# thermokoppel.net
KiCad netlist of a schematic drawn in Altium Designer
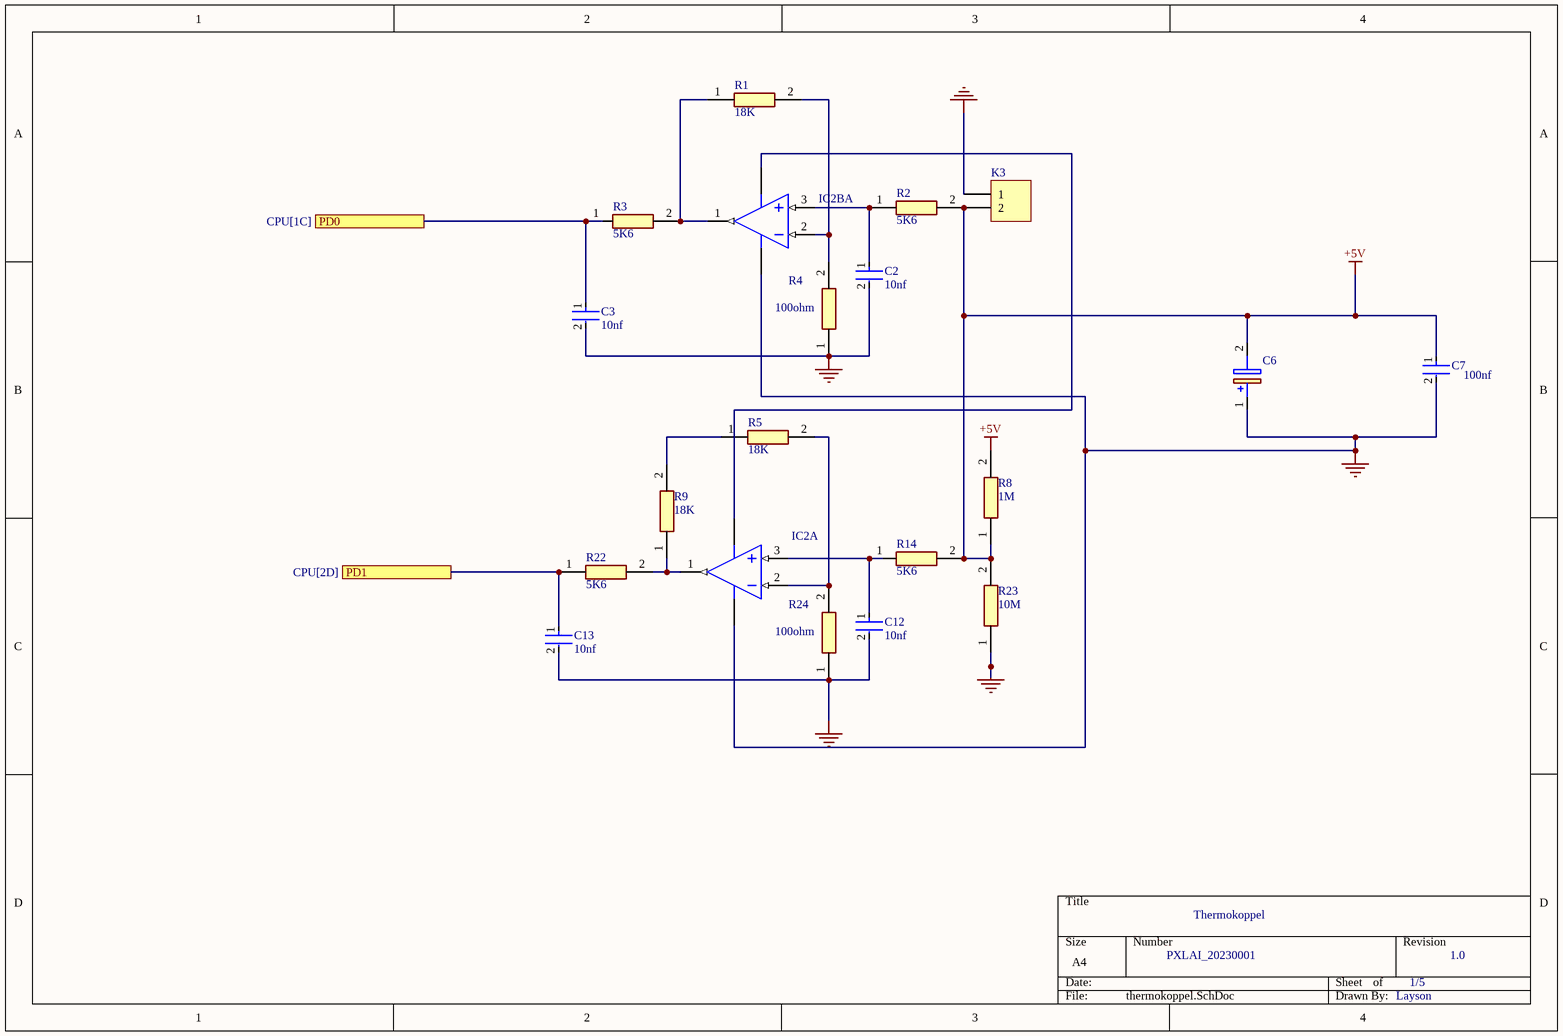
[diagram p0: thermokoppel.SchDoc]

(export (version "E")
  (design (tool "Eeschema 10.0.6"))
  (components
    (comp (ref "C2")
      (value "10nf")
      (footprint "FP-RDE0M1-MFG")
      (description "Ceramic Capacitor 10nF ±10% 50V X7R Radial")
      (fields (field (name "TOLERANCE") "10%"))
      (libsource (lib "Altium Content Vault") (part "b4654b650e69147ec39a6b967a45e02"))
    )
    (comp (ref "C3")
      (value "10nf")
      (footprint "FP-RDE0M1-MFG")
      (description "Ceramic Capacitor 10nF ±10% 50V X7R Radial")
      (fields (field (name "TOLERANCE") "10%"))
      (libsource (lib "Altium Content Vault") (part "b4654b650e69147ec39a6b967a45e02"))
    )
    (comp (ref "C6")
      (value "MCGPR50V106M5X11")
      (footprint "SamacSys:CAPPRD200W52D525H1200")
      (description "Capacitor Polarised")
      (libsource (lib "*") (part "MCGPR50V106M5X11"))
    )
    (comp (ref "C7")
      (value "100nf")
      (footprint "FP-C0402-BB-MFG")
      (description "CAP CER 0.1UF 10V X5R 0402")
      (fields (field (name "MANUFACTURER") "Kemet") (field (name "TOLERANCE") "0.1"))
      (libsource (lib "Altium Content Vault") (part "b4654b650e69147ec39a6b967a45e02"))
    )
    (comp (ref "C12")
      (value "10nf")
      (footprint "FP-RDE0M1-MFG")
      (description "Ceramic Capacitor 10nF ±10% 50V X7R Radial")
      (fields (field (name "TOLERANCE") "10%"))
      (libsource (lib "Altium Content Vault") (part "b4654b650e69147ec39a6b967a45e02"))
    )
    (comp (ref "C13")
      (value "10nf")
      (footprint "FP-RDE0M1-MFG")
      (description "Ceramic Capacitor 10nF ±10% 50V X7R Radial")
      (fields (field (name "TOLERANCE") "10%"))
      (libsource (lib "Altium Content Vault") (part "b4654b650e69147ec39a6b967a45e02"))
    )
    (comp (ref "IC2")
      (value "IC2A")
      (footprint "SOIC-SN8_M")
      (description "None")
      (libsource (lib "Altium Content Vault") (part "AMP-OPA-MCP6002-IL8"))
    )
    (comp (ref "IC2B")
      (value "MCP6002-E/MS")
      (footprint "MSOP-MS8_M")
      (description "None")
      (libsource (lib "") (part "AMP-OPA-MCP6002-IL8_1"))
    )
    (comp (ref "K3")
      (value "Header 2")
      (footprint "HDR1X2")
      (description "Header, 2-Pin")
      (fields (field (name "PUBLISHER") "Altium Limited"))
      (libsource (lib "Miscellaneous Connectors") (part "Header 2"))
    )
    (comp (ref "R1")
      (value "18K")
      (footprint "SamacSys:RESC2012X65N")
      (description "Resistor\r\nCPF0805B18KE")
      (fields
        (field (name "MANUFACTURER_PART_NUMBER") "CPF0805B18KE")
        (field (name "MOUSER PART NUMBER") "279-CPF0805B18KE")
      )
      (libsource (lib "*") (part "CPF0805B18KE"))
    )
    (comp (ref "R2")
      (value "5K6")
      (footprint "SamacSys:RESC2012X65N")
      (description "Resistor\r\nCPF0805B5K62E")
      (fields (field (name "MANUFACTURER_PART_NUMBER") "CPF0805B5K62E"))
      (libsource (lib "*") (part "CPF0805B5K62E"))
    )
    (comp (ref "R3")
      (value "5K6")
      (footprint "SamacSys:RESC2012X65N")
      (description "Resistor\r\nCPF0805B5K62E")
      (fields (field (name "MANUFACTURER_PART_NUMBER") "CPF0805B5K62E"))
      (libsource (lib "*") (part "CPF0805B5K62E"))
    )
    (comp (ref "R4")
      (value "100ohm")
      (footprint "SamacSys:RESC2012X60N")
      (description "Resistor\r\nCR0805-JW-101ELF")
      (fields
        (field (name "MANUFACTURER_PART_NUMBER") "CR0805-JW-101ELF")
        (field (name "MOUSER PART NUMBER") "652-CR0805JW-101ELF")
      )
      (libsource (lib "*") (part "CR0805-JW-101ELF"))
    )
    (comp (ref "R5")
      (value "18K")
      (footprint "SamacSys:RESC2012X65N")
      (description "Resistor\r\nCPF0805B18KE")
      (fields
        (field (name "MANUFACTURER_PART_NUMBER") "CPF0805B18KE")
        (field (name "MOUSER PART NUMBER") "279-CPF0805B18KE")
      )
      (libsource (lib "*") (part "CPF0805B18KE"))
    )
    (comp (ref "R8")
      (value "1M")
      (footprint "SamacSys:RESC2012X65N")
      (description "Resistor\r\nCPF0805B1M0E")
      (fields (field (name "MANUFACTURER_PART_NUMBER") "CPF0805B1M0E"))
      (libsource (lib "*") (part "CPF0805B1M0E"))
    )
    (comp (ref "R9")
      (value "18K")
      (footprint "SamacSys:RESC2012X65N")
      (description "Resistor\r\nCPF0805B18KE")
      (fields
        (field (name "MANUFACTURER_PART_NUMBER") "CPF0805B18KE")
        (field (name "MOUSER PART NUMBER") "279-CPF0805B18KE")
      )
      (libsource (lib "") (part "CPF0805B18KE_1"))
    )
    (comp (ref "R14")
      (value "5K6")
      (footprint "SamacSys:RESC2012X65N")
      (description "Resistor\r\nCPF0805B5K62E")
      (fields (field (name "MANUFACTURER_PART_NUMBER") "CPF0805B5K62E"))
      (libsource (lib "*") (part "CPF0805B5K62E"))
    )
    (comp (ref "R22")
      (value "5K6")
      (footprint "SamacSys:RESC2012X65N")
      (description "Resistor\r\nCPF0805B5K62E")
      (fields (field (name "MANUFACTURER_PART_NUMBER") "CPF0805B5K62E"))
      (libsource (lib "*") (part "CPF0805B5K62E"))
    )
    (comp (ref "R23")
      (value "10M")
      (footprint "SamacSys:RESC2013X65N")
      (description "Resistor\r\nCRGH0805J10M")
      (fields
        (field (name "MANUFACTURER_PART_NUMBER") "CRGH0805J10M")
        (field (name "MOUSER PART NUMBER") "279-CRGH0805J10M")
      )
      (libsource (lib "*") (part "CRGH0805J10M"))
    )
    (comp (ref "R24")
      (value "100ohm")
      (footprint "SamacSys:RESC2012X60N")
      (description "Resistor\r\nCR0805-JW-101ELF")
      (fields
        (field (name "MANUFACTURER_PART_NUMBER") "CR0805-JW-101ELF")
        (field (name "MOUSER PART NUMBER") "652-CR0805JW-101ELF")
      )
      (libsource (lib "*") (part "CR0805-JW-101ELF"))
    )
  )
  (nets
    (net (code "1") (name "+5V") (class "Default")
      (node (ref "C6") (pin "2") (pinfunction "-_2") (pintype "passive"))
      (node (ref "C7") (pin "1") (pinfunction "1_1") (pintype "passive"))
      (node (ref "K3") (pin "2") (pinfunction "2_2") (pintype "passive"))
      (node (ref "R14") (pin "2") (pinfunction "2_2") (pintype "passive"))
      (node (ref "R2") (pin "2") (pinfunction "2_2") (pintype "passive"))
      (node (ref "R23") (pin "2") (pinfunction "2_2") (pintype "passive"))
      (node (ref "R8") (pin "1") (pinfunction "1_1") (pintype "passive"))
      (node (ref "R8") (pin "2") (pinfunction "2_2") (pintype "passive"))
    )
    (net (code "2") (name "/PD0") (class "Default")
      (node (ref "C3") (pin "1") (pinfunction "1_1") (pintype "passive"))
      (node (ref "R3") (pin "1") (pinfunction "1_1") (pintype "passive"))
    )
    (net (code "3") (name "/PD1") (class "Default")
      (node (ref "C13") (pin "1") (pinfunction "1_1") (pintype "passive"))
      (node (ref "R22") (pin "1") (pinfunction "1_1") (pintype "passive"))
    )
    (net (code "4") (name "GND") (class "Default")
      (node (ref "C12") (pin "2") (pinfunction "2_2") (pintype "passive"))
      (node (ref "C13") (pin "2") (pinfunction "2_2") (pintype "passive"))
      (node (ref "C2") (pin "2") (pinfunction "2_2") (pintype "passive"))
      (node (ref "C3") (pin "2") (pinfunction "2_2") (pintype "passive"))
      (node (ref "C6") (pin "1") (pinfunction "+_1") (pintype "passive"))
      (node (ref "C7") (pin "2") (pinfunction "2_2") (pintype "passive"))
      (node (ref "IC2") (pin "8") (pinfunction "VDD_8") (pintype "power_in"))
      (node (ref "IC2B") (pin "8") (pinfunction "VDD_8") (pintype "power_in"))
      (node (ref "K3") (pin "1") (pinfunction "1_1") (pintype "passive"))
      (node (ref "R23") (pin "1") (pinfunction "1_1") (pintype "passive"))
      (node (ref "R24") (pin "1") (pinfunction "1_1") (pintype "passive"))
      (node (ref "R4") (pin "1") (pinfunction "1_1") (pintype "passive"))
    )
    (net (code "5") (name "Net-(IC2A-VINA+)") (class "Default")
      (node (ref "C12") (pin "1") (pinfunction "1_1") (pintype "passive"))
      (node (ref "IC2") (pin "3") (pinfunction "VINA+_3") (pintype "input"))
      (node (ref "R14") (pin "1") (pinfunction "1_1") (pintype "passive"))
    )
    (net (code "6") (name "Net-(IC2A-VINA-)") (class "Default")
      (node (ref "IC2") (pin "2") (pinfunction "VINA-_2") (pintype "input"))
      (node (ref "R24") (pin "2") (pinfunction "2_2") (pintype "passive"))
      (node (ref "R5") (pin "2") (pinfunction "2_2") (pintype "passive"))
    )
    (net (code "7") (name "Net-(IC2A-VOUTA)") (class "Default")
      (node (ref "IC2") (pin "1") (pinfunction "VOUTA_1") (pintype "output"))
      (node (ref "R22") (pin "2") (pinfunction "2_2") (pintype "passive"))
      (node (ref "R9") (pin "1") (pinfunction "1_1") (pintype "passive"))
    )
    (net (code "8") (name "Net-(IC2A-VSS)") (class "Default")
      (node (ref "IC2") (pin "4") (pinfunction "VSS_4") (pintype "power_in"))
      (node (ref "IC2B") (pin "4") (pinfunction "VSS_4") (pintype "power_in"))
    )
    (net (code "9") (name "Net-(IC2BA-VINA+)") (class "Default")
      (node (ref "C2") (pin "1") (pinfunction "1_1") (pintype "passive"))
      (node (ref "IC2B") (pin "3") (pinfunction "VINA+_3") (pintype "input"))
      (node (ref "R2") (pin "1") (pinfunction "1_1") (pintype "passive"))
    )
    (net (code "10") (name "Net-(IC2BA-VINA-)") (class "Default")
      (node (ref "IC2B") (pin "2") (pinfunction "VINA-_2") (pintype "input"))
      (node (ref "R1") (pin "2") (pinfunction "2_2") (pintype "passive"))
      (node (ref "R4") (pin "2") (pinfunction "2_2") (pintype "passive"))
    )
    (net (code "11") (name "Net-(IC2BA-VOUTA)") (class "Default")
      (node (ref "IC2B") (pin "1") (pinfunction "VOUTA_1") (pintype "output"))
      (node (ref "R1") (pin "1") (pinfunction "1_1") (pintype "passive"))
      (node (ref "R3") (pin "2") (pinfunction "2_2") (pintype "passive"))
    )
    (net (code "12") (name "Net-(R5-Pad1)") (class "Default")
      (node (ref "R5") (pin "1") (pinfunction "1_1") (pintype "passive"))
      (node (ref "R9") (pin "2") (pinfunction "2_2") (pintype "passive"))
    )
  )
)
